# Up.net
KiCad netlist of a schematic drawn in EAGLE
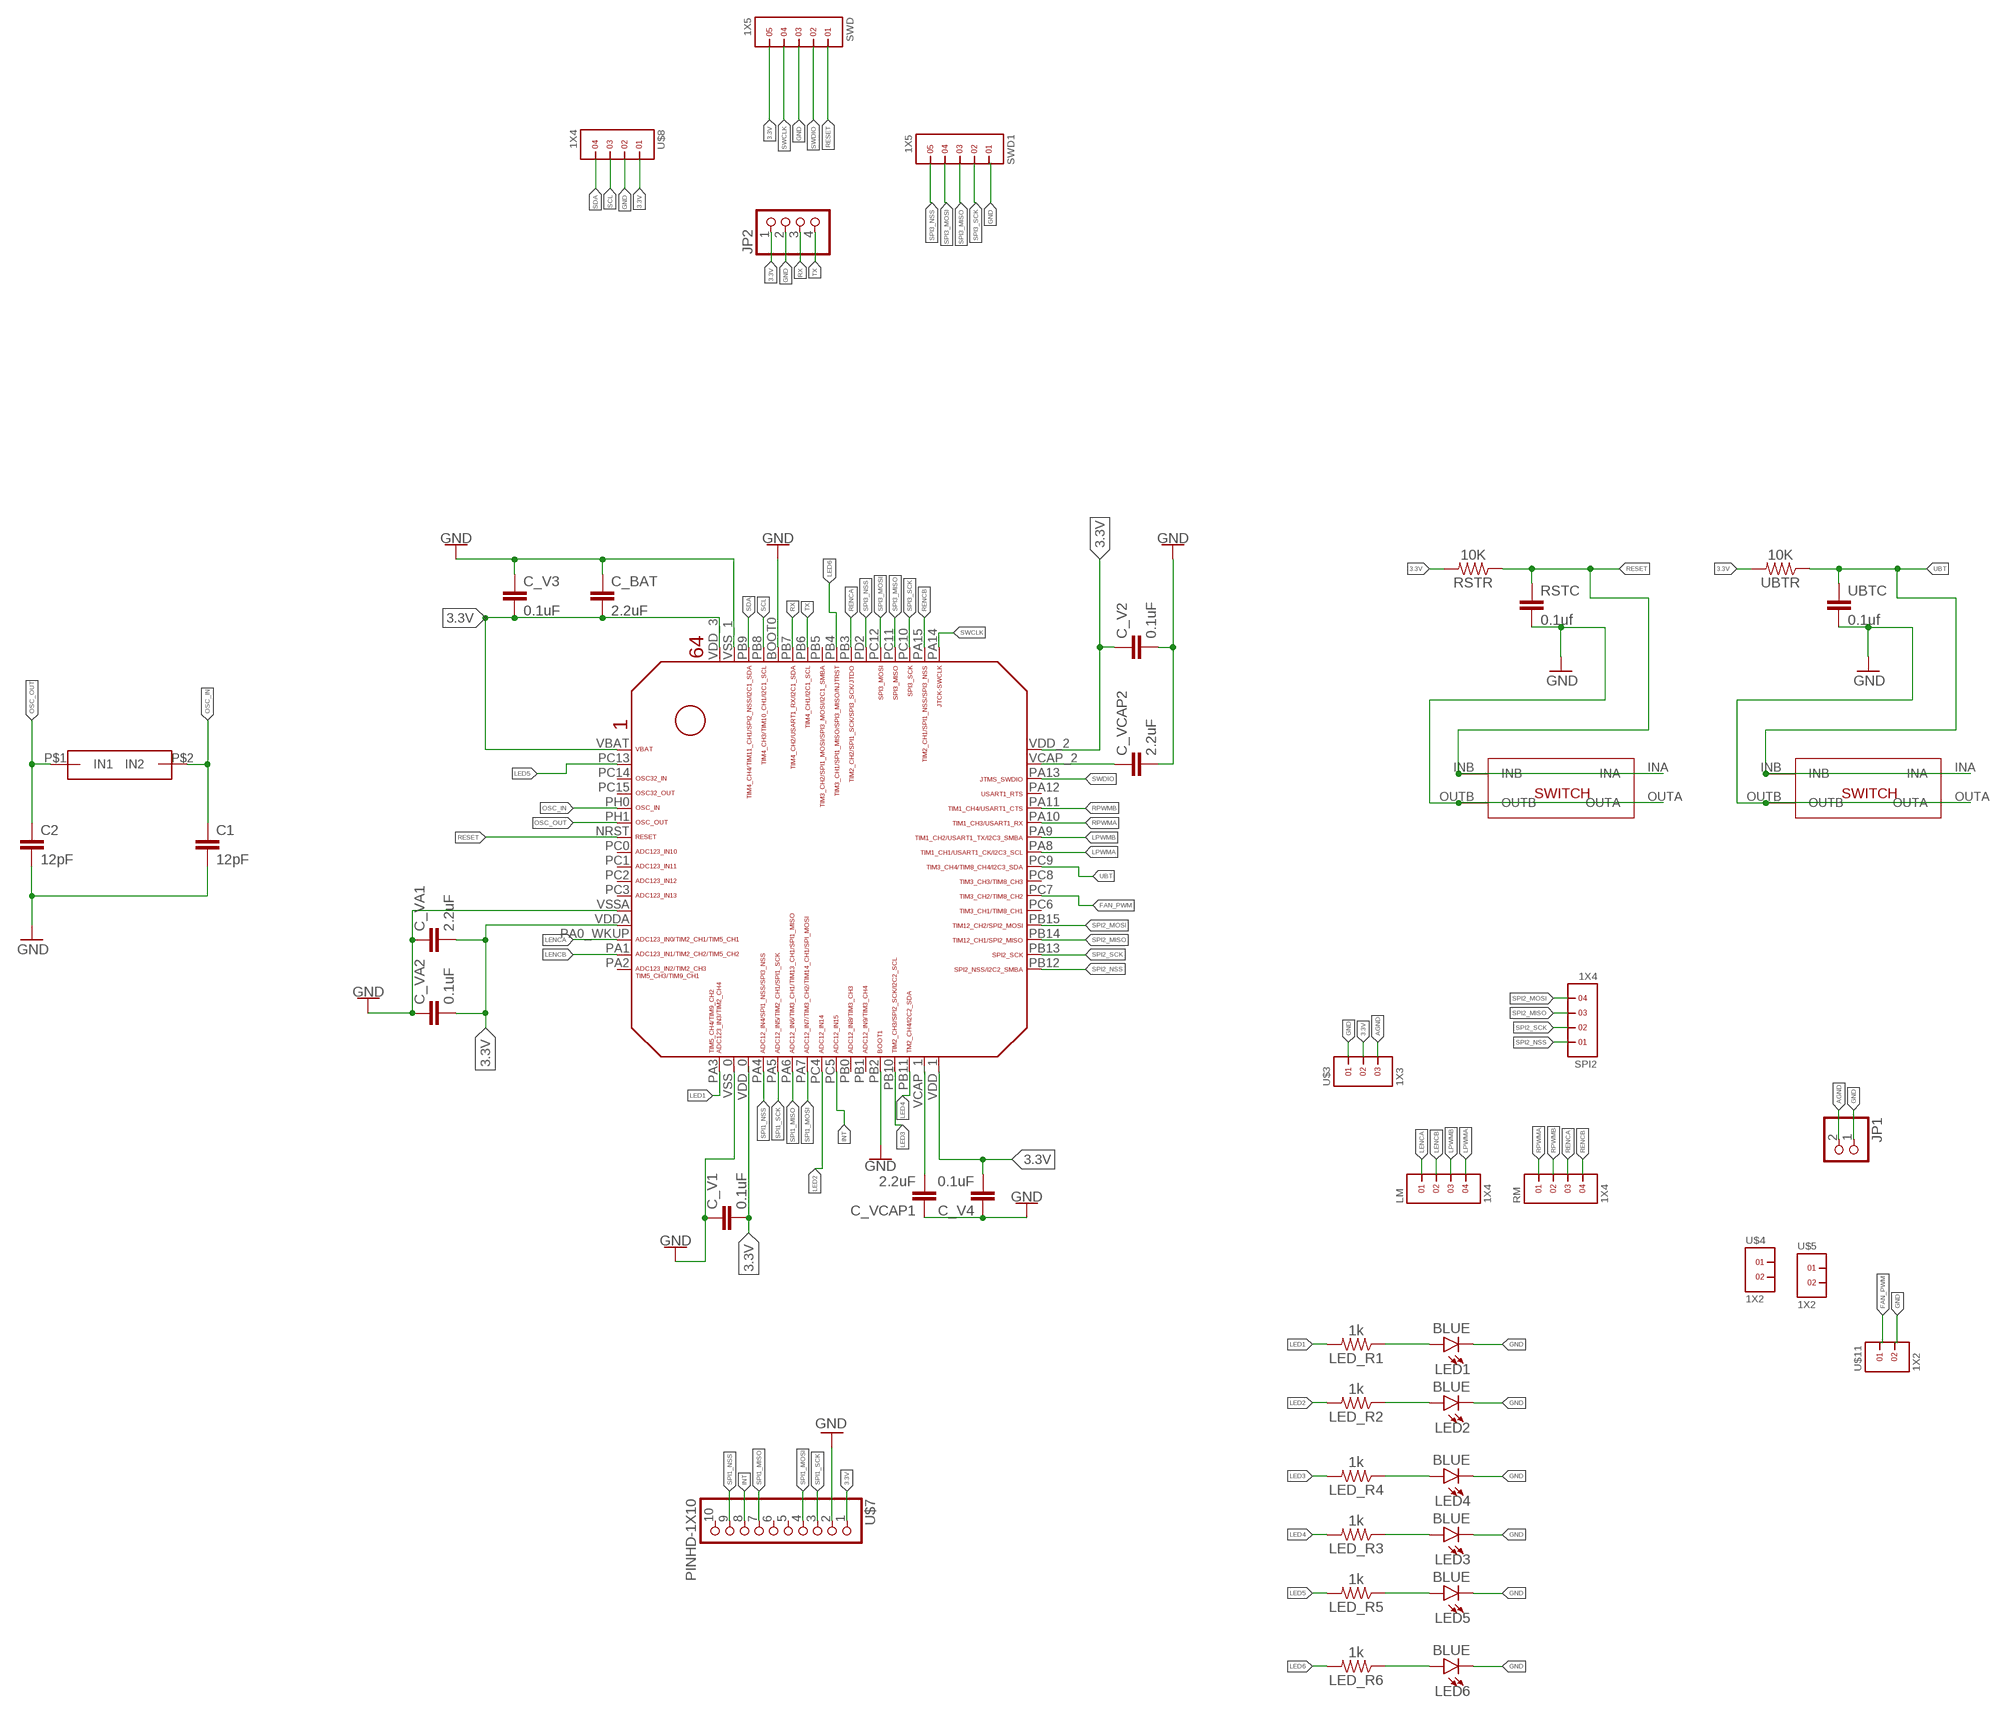
[diagram p0: schematic, sheet 1]

(export (version "E")
  (design (tool "Eeschema 10.0.6"))
  (components
    (comp (ref "C1")
      (value "12pF")
      (footprint "eagle-import:0603")
      (libsource (lib "eagle-import") (part "22PF-0603-50V-5%"))
    )
    (comp (ref "C2")
      (value "12pF")
      (footprint "eagle-import:0603")
      (libsource (lib "eagle-import") (part "22PF-0603-50V-5%"))
    )
    (comp (ref "CX5032GA*8MHZ*CYSTAL")
      (value "OSC")
      (footprint "eagle-import:OSC")
      (libsource (lib "eagle-import") (part "OSC"))
    )
    (comp (ref "C_BAT")
      (value "2.2uF")
      (footprint "eagle-import:0805")
      (libsource (lib "eagle-import") (part "22UF-0805-6.3V-20%"))
    )
    (comp (ref "C_V1")
      (value "0.1uF")
      (footprint "eagle-import:0805")
      (libsource (lib "eagle-import") (part "22UF-0805-6.3V-20%"))
    )
    (comp (ref "C_V2")
      (value "0.1uF")
      (footprint "eagle-import:0805")
      (libsource (lib "eagle-import") (part "22UF-0805-6.3V-20%"))
    )
    (comp (ref "C_V3")
      (value "0.1uF")
      (footprint "eagle-import:0805")
      (libsource (lib "eagle-import") (part "22UF-0805-6.3V-20%"))
    )
    (comp (ref "C_V4")
      (value "0.1uF")
      (footprint "eagle-import:0805")
      (libsource (lib "eagle-import") (part "22UF-0805-6.3V-20%"))
    )
    (comp (ref "C_VA1")
      (value "2.2uF")
      (footprint "eagle-import:0805")
      (libsource (lib "eagle-import") (part "22UF-0805-6.3V-20%"))
    )
    (comp (ref "C_VA2")
      (value "0.1uF")
      (footprint "eagle-import:0805")
      (libsource (lib "eagle-import") (part "22UF-0805-6.3V-20%"))
    )
    (comp (ref "C_VCAP1")
      (value "2.2uF")
      (footprint "eagle-import:0805")
      (libsource (lib "eagle-import") (part "22UF-0805-6.3V-20%"))
    )
    (comp (ref "C_VCAP2")
      (value "2.2uF")
      (footprint "eagle-import:0805")
      (libsource (lib "eagle-import") (part "22UF-0805-6.3V-20%"))
    )
    (comp (ref "JP1")
      (value "PINHD-1X2")
      (footprint "eagle-import:1X02")
      (libsource (lib "eagle-import") (part "PINHD-1X2"))
    )
    (comp (ref "JP2")
      (value "PINHD-1X4")
      (footprint "eagle-import:1X04")
      (libsource (lib "eagle-import") (part "PINHD-1X4"))
    )
    (comp (ref "LED1")
      (value "BLUE")
      (footprint "eagle-import:LED-1206")
      (libsource (lib "eagle-import") (part "LED-BLUE1206"))
    )
    (comp (ref "LED2")
      (value "BLUE")
      (footprint "eagle-import:LED-1206")
      (libsource (lib "eagle-import") (part "LED-BLUE1206"))
    )
    (comp (ref "LED3")
      (value "BLUE")
      (footprint "eagle-import:LED-1206")
      (libsource (lib "eagle-import") (part "LED-BLUE1206"))
    )
    (comp (ref "LED4")
      (value "BLUE")
      (footprint "eagle-import:LED-1206")
      (libsource (lib "eagle-import") (part "LED-BLUE1206"))
    )
    (comp (ref "LED5")
      (value "BLUE")
      (footprint "eagle-import:LED-1206")
      (libsource (lib "eagle-import") (part "LED-BLUE1206"))
    )
    (comp (ref "LED6")
      (value "BLUE")
      (footprint "eagle-import:LED-1206")
      (libsource (lib "eagle-import") (part "LED-BLUE1206"))
    )
    (comp (ref "LED_R1")
      (value "1k")
      (footprint "eagle-import:0805")
      (libsource (lib "eagle-import") (part "0.75OHM-0805-1/4W-1%"))
    )
    (comp (ref "LED_R2")
      (value "1k")
      (footprint "eagle-import:0805")
      (libsource (lib "eagle-import") (part "0.75OHM-0805-1/4W-1%"))
    )
    (comp (ref "LED_R3")
      (value "1k")
      (footprint "eagle-import:0805")
      (libsource (lib "eagle-import") (part "0.75OHM-0805-1/4W-1%"))
    )
    (comp (ref "LED_R4")
      (value "1k")
      (footprint "eagle-import:0805")
      (libsource (lib "eagle-import") (part "0.75OHM-0805-1/4W-1%"))
    )
    (comp (ref "LED_R5")
      (value "1k")
      (footprint "eagle-import:0805")
      (libsource (lib "eagle-import") (part "0.75OHM-0805-1/4W-1%"))
    )
    (comp (ref "LED_R6")
      (value "1k")
      (footprint "eagle-import:0805")
      (libsource (lib "eagle-import") (part "0.75OHM-0805-1/4W-1%"))
    )
    (comp (ref "LM")
      (value "1X4")
      (footprint "eagle-import:1X4")
      (libsource (lib "eagle-import") (part "1X4"))
    )
    (comp (ref "RM")
      (value "1X4")
      (footprint "eagle-import:1X4")
      (libsource (lib "eagle-import") (part "1X4"))
    )
    (comp (ref "RSTC")
      (value "0.1uf")
      (footprint "eagle-import:0805")
      (libsource (lib "eagle-import") (part "22UF-0805-6.3V-20%"))
    )
    (comp (ref "RSTR")
      (value "10K")
      (footprint "eagle-import:0805")
      (libsource (lib "eagle-import") (part "0.75OHM-0805-1/4W-1%"))
    )
    (comp (ref "SPI2")
      (value "1X4")
      (footprint "eagle-import:1X4")
      (libsource (lib "eagle-import") (part "1X4"))
    )
    (comp (ref "SWD")
      (value "1X5")
      (footprint "eagle-import:1X5")
      (libsource (lib "eagle-import") (part "1X5"))
    )
    (comp (ref "SWD1")
      (value "1X5")
      (footprint "eagle-import:1X5")
      (libsource (lib "eagle-import") (part "1X5"))
    )
    (comp (ref "U$1")
      (value "STM32F405/415_LQFP64")
      (footprint "eagle-import:STM32F405_415_LQFP64")
      (libsource (lib "eagle-import") (part "STM32F405/415_LQFP64"))
    )
    (comp (ref "U$3")
      (value "1X3")
      (footprint "eagle-import:1X3")
      (libsource (lib "eagle-import") (part "1X3"))
    )
    (comp (ref "U$4")
      (value "1X2")
      (footprint "eagle-import:1X2")
      (libsource (lib "eagle-import") (part "1X2"))
    )
    (comp (ref "U$5")
      (value "1X2")
      (footprint "eagle-import:1X2")
      (libsource (lib "eagle-import") (part "1X2"))
    )
    (comp (ref "U$7")
      (value "PINHD-1X10")
      (footprint "eagle-import:1X10-BIG")
      (libsource (lib "eagle-import") (part "PINHD-1X10"))
    )
    (comp (ref "U$8")
      (value "1X4")
      (footprint "eagle-import:1X4")
      (libsource (lib "eagle-import") (part "1X4"))
    )
    (comp (ref "U$9")
      (value "4X4X1.5_SMD_SWITCH")
      (footprint "eagle-import:4X4X1.5_SMD_SWITCH")
      (libsource (lib "eagle-import") (part "4X4X1.5_SMD_SWITCH"))
    )
    (comp (ref "U$10")
      (value "4X4X1.5_SMD_SWITCH")
      (footprint "eagle-import:4X4X1.5_SMD_SWITCH")
      (libsource (lib "eagle-import") (part "4X4X1.5_SMD_SWITCH"))
    )
    (comp (ref "U$11")
      (value "1X2")
      (footprint "eagle-import:1X2")
      (libsource (lib "eagle-import") (part "1X2"))
    )
    (comp (ref "UBTC")
      (value "0.1uf")
      (footprint "eagle-import:0805")
      (libsource (lib "eagle-import") (part "22UF-0805-6.3V-20%"))
    )
    (comp (ref "UBTR")
      (value "10K")
      (footprint "eagle-import:0805")
      (libsource (lib "eagle-import") (part "0.75OHM-0805-1/4W-1%"))
    )
  )
  (nets
    (net (code "1") (name "3.3V") (class "Default")
      (node (ref "C_BAT") (pin "2") (pinfunction "2_2") (pintype "passive"))
      (node (ref "C_V1") (pin "2") (pinfunction "2_2") (pintype "passive"))
      (node (ref "C_V2") (pin "1") (pinfunction "1_1") (pintype "passive"))
      (node (ref "C_V3") (pin "2") (pinfunction "2_2") (pintype "passive"))
      (node (ref "C_V4") (pin "2") (pinfunction "2_2") (pintype "passive"))
      (node (ref "C_VA1") (pin "2") (pinfunction "2_2") (pintype "passive"))
      (node (ref "C_VA2") (pin "2") (pinfunction "2_2") (pintype "passive"))
      (node (ref "JP2") (pin "1") (pinfunction "1_1") (pintype "passive"))
      (node (ref "RSTR") (pin "2") (pinfunction "2_2") (pintype "passive"))
      (node (ref "SWD") (pin "5") (pinfunction "5_5") (pintype "bidirectional"))
      (node (ref "U$1") (pin "VBAT") (pinfunction "VBAT_VBAT") (pintype "bidirectional"))
      (node (ref "U$1") (pin "VDDA") (pinfunction "VDDA_VDDA") (pintype "bidirectional"))
      (node (ref "U$1") (pin "VDD_0") (pinfunction "VDD_0_VDD_0") (pintype "bidirectional"))
      (node (ref "U$1") (pin "VDD_1") (pinfunction "VDD_1_VDD_1") (pintype "bidirectional"))
      (node (ref "U$1") (pin "VDD_2") (pinfunction "VDD_2_VDD_2") (pintype "bidirectional"))
      (node (ref "U$1") (pin "VDD_3") (pinfunction "VDD_3_VDD_3") (pintype "bidirectional"))
      (node (ref "U$3") (pin "2") (pinfunction "2_2") (pintype "bidirectional"))
      (node (ref "U$7") (pin "1") (pinfunction "1_1") (pintype "passive"))
      (node (ref "U$8") (pin "1") (pinfunction "1_1") (pintype "bidirectional"))
      (node (ref "UBTR") (pin "2") (pinfunction "2_2") (pintype "passive"))
    )
    (net (code "2") (name "AGND") (class "Default")
      (node (ref "JP1") (pin "2") (pinfunction "2_2") (pintype "passive"))
      (node (ref "U$3") (pin "3") (pinfunction "3_3") (pintype "bidirectional"))
    )
    (net (code "3") (name "FAN_PWM") (class "Default")
      (node (ref "U$1") (pin "PC7") (pinfunction "PC7_PC7") (pintype "bidirectional"))
      (node (ref "U$11") (pin "1") (pinfunction "1_1") (pintype "bidirectional"))
    )
    (net (code "4") (name "GND") (class "Default")
      (node (ref "C1") (pin "2") (pinfunction "2_2") (pintype "passive"))
      (node (ref "C2") (pin "2") (pinfunction "2_2") (pintype "passive"))
      (node (ref "C_BAT") (pin "1") (pinfunction "1_1") (pintype "passive"))
      (node (ref "C_V1") (pin "1") (pinfunction "1_1") (pintype "passive"))
      (node (ref "C_V2") (pin "2") (pinfunction "2_2") (pintype "passive"))
      (node (ref "C_V3") (pin "1") (pinfunction "1_1") (pintype "passive"))
      (node (ref "C_V4") (pin "1") (pinfunction "1_1") (pintype "passive"))
      (node (ref "C_VA1") (pin "1") (pinfunction "1_1") (pintype "passive"))
      (node (ref "C_VA2") (pin "1") (pinfunction "1_1") (pintype "passive"))
      (node (ref "C_VCAP1") (pin "1") (pinfunction "1_1") (pintype "passive"))
      (node (ref "C_VCAP2") (pin "2") (pinfunction "2_2") (pintype "passive"))
      (node (ref "JP1") (pin "1") (pinfunction "1_1") (pintype "passive"))
      (node (ref "JP2") (pin "2") (pinfunction "2_2") (pintype "passive"))
      (node (ref "LED1") (pin "C") (pinfunction "C_C") (pintype "passive"))
      (node (ref "LED2") (pin "C") (pinfunction "C_C") (pintype "passive"))
      (node (ref "LED3") (pin "C") (pinfunction "C_C") (pintype "passive"))
      (node (ref "LED4") (pin "C") (pinfunction "C_C") (pintype "passive"))
      (node (ref "LED5") (pin "C") (pinfunction "C_C") (pintype "passive"))
      (node (ref "LED6") (pin "C") (pinfunction "C_C") (pintype "passive"))
      (node (ref "RSTC") (pin "2") (pinfunction "2_2") (pintype "passive"))
      (node (ref "SWD") (pin "3") (pinfunction "3_3") (pintype "bidirectional"))
      (node (ref "SWD1") (pin "1") (pinfunction "1_1") (pintype "bidirectional"))
      (node (ref "U$1") (pin "BOOT0") (pinfunction "BOOT0_BOOT0") (pintype "bidirectional"))
      (node (ref "U$1") (pin "PB2") (pinfunction "PB2_PB2") (pintype "bidirectional"))
      (node (ref "U$1") (pin "VSSA") (pinfunction "VSSA_VSSA") (pintype "bidirectional"))
      (node (ref "U$1") (pin "VSS_0") (pinfunction "VSS_0_VSS_0") (pintype "bidirectional"))
      (node (ref "U$1") (pin "VSS_1") (pinfunction "VSS_1_VSS_1") (pintype "bidirectional"))
      (node (ref "U$10") (pin "OUTA") (pinfunction "OUTA_OUTA") (pintype "bidirectional"))
      (node (ref "U$10") (pin "OUTB") (pinfunction "OUTB_OUTB") (pintype "bidirectional"))
      (node (ref "U$11") (pin "2") (pinfunction "2_2") (pintype "bidirectional"))
      (node (ref "U$3") (pin "1") (pinfunction "1_1") (pintype "bidirectional"))
      (node (ref "U$7") (pin "2") (pinfunction "2_2") (pintype "passive"))
      (node (ref "U$8") (pin "2") (pinfunction "2_2") (pintype "bidirectional"))
      (node (ref "U$9") (pin "OUTA") (pinfunction "OUTA_OUTA") (pintype "bidirectional"))
      (node (ref "U$9") (pin "OUTB") (pinfunction "OUTB_OUTB") (pintype "bidirectional"))
      (node (ref "UBTC") (pin "2") (pinfunction "2_2") (pintype "passive"))
    )
    (net (code "5") (name "INT") (class "Default")
      (node (ref "U$1") (pin "PC5") (pinfunction "PC5_PC5") (pintype "bidirectional"))
      (node (ref "U$7") (pin "8") (pinfunction "8_8") (pintype "passive"))
    )
    (net (code "6") (name "LED1") (class "Default")
      (node (ref "LED_R1") (pin "2") (pinfunction "2_2") (pintype "passive"))
      (node (ref "U$1") (pin "PA3") (pinfunction "PA3_PA3") (pintype "bidirectional"))
    )
    (net (code "7") (name "LED2") (class "Default")
      (node (ref "LED_R2") (pin "2") (pinfunction "2_2") (pintype "passive"))
      (node (ref "U$1") (pin "PC4") (pinfunction "PC4_PC4") (pintype "bidirectional"))
    )
    (net (code "8") (name "LED3") (class "Default")
      (node (ref "LED_R4") (pin "2") (pinfunction "2_2") (pintype "passive"))
      (node (ref "U$1") (pin "PB10") (pinfunction "PB10_PB10") (pintype "bidirectional"))
    )
    (net (code "9") (name "LED4") (class "Default")
      (node (ref "LED_R3") (pin "2") (pinfunction "2_2") (pintype "passive"))
      (node (ref "U$1") (pin "PB11") (pinfunction "PB11_PB11") (pintype "bidirectional"))
    )
    (net (code "10") (name "LED5") (class "Default")
      (node (ref "LED_R5") (pin "2") (pinfunction "2_2") (pintype "passive"))
      (node (ref "U$1") (pin "PC13") (pinfunction "PC13_PC13") (pintype "bidirectional"))
    )
    (net (code "11") (name "LED6") (class "Default")
      (node (ref "LED_R6") (pin "2") (pinfunction "2_2") (pintype "passive"))
      (node (ref "U$1") (pin "PB4") (pinfunction "PB4_PB4") (pintype "bidirectional"))
    )
    (net (code "12") (name "LENCA") (class "Default")
      (node (ref "LM") (pin "1") (pinfunction "1_1") (pintype "bidirectional"))
      (node (ref "U$1") (pin "PA0_WKUP") (pinfunction "PA0_AKUP_PA0_WKUP") (pintype "bidirectional"))
    )
    (net (code "13") (name "LENCB") (class "Default")
      (node (ref "LM") (pin "2") (pinfunction "2_2") (pintype "bidirectional"))
      (node (ref "U$1") (pin "PA1") (pinfunction "PA1_PA1") (pintype "bidirectional"))
    )
    (net (code "14") (name "LPWMA") (class "Default")
      (node (ref "LM") (pin "4") (pinfunction "4_4") (pintype "bidirectional"))
      (node (ref "U$1") (pin "PA8") (pinfunction "PA8_PA8") (pintype "bidirectional"))
    )
    (net (code "15") (name "LPWMB") (class "Default")
      (node (ref "LM") (pin "3") (pinfunction "3_3") (pintype "bidirectional"))
      (node (ref "U$1") (pin "PA9") (pinfunction "PA9_PA9") (pintype "bidirectional"))
    )
    (net (code "16") (name "Net-(C_VCAP1-Pad2)") (class "Default")
      (node (ref "C_VCAP1") (pin "2") (pinfunction "2_2") (pintype "passive"))
      (node (ref "U$1") (pin "VCAP_1") (pinfunction "VCAP_1_VCAP_1") (pintype "bidirectional"))
    )
    (net (code "17") (name "Net-(C_VCAP2-Pad1)") (class "Default")
      (node (ref "C_VCAP2") (pin "1") (pinfunction "1_1") (pintype "passive"))
      (node (ref "U$1") (pin "VCAP_2") (pinfunction "VCAP_2_VCAP_2") (pintype "bidirectional"))
    )
    (net (code "18") (name "Net-(LED1-PadA)") (class "Default")
      (node (ref "LED1") (pin "A") (pinfunction "A_A") (pintype "passive"))
      (node (ref "LED_R1") (pin "1") (pinfunction "1_1") (pintype "passive"))
    )
    (net (code "19") (name "Net-(LED2-PadA)") (class "Default")
      (node (ref "LED2") (pin "A") (pinfunction "A_A") (pintype "passive"))
      (node (ref "LED_R2") (pin "1") (pinfunction "1_1") (pintype "passive"))
    )
    (net (code "20") (name "Net-(LED3-PadA)") (class "Default")
      (node (ref "LED3") (pin "A") (pinfunction "A_A") (pintype "passive"))
      (node (ref "LED_R3") (pin "1") (pinfunction "1_1") (pintype "passive"))
    )
    (net (code "21") (name "Net-(LED4-PadA)") (class "Default")
      (node (ref "LED4") (pin "A") (pinfunction "A_A") (pintype "passive"))
      (node (ref "LED_R4") (pin "1") (pinfunction "1_1") (pintype "passive"))
    )
    (net (code "22") (name "Net-(LED5-PadA)") (class "Default")
      (node (ref "LED5") (pin "A") (pinfunction "A_A") (pintype "passive"))
      (node (ref "LED_R5") (pin "1") (pinfunction "1_1") (pintype "passive"))
    )
    (net (code "23") (name "Net-(LED6-PadA)") (class "Default")
      (node (ref "LED6") (pin "A") (pinfunction "A_A") (pintype "passive"))
      (node (ref "LED_R6") (pin "1") (pinfunction "1_1") (pintype "passive"))
    )
    (net (code "24") (name "OSC_IN") (class "Default")
      (node (ref "C1") (pin "1") (pinfunction "1_1") (pintype "passive"))
      (node (ref "CX5032GA*8MHZ*CYSTAL") (pin "P$2") (pinfunction "IN2_P$2") (pintype "bidirectional"))
      (node (ref "U$1") (pin "PH0") (pinfunction "PH0_PH0") (pintype "bidirectional"))
    )
    (net (code "25") (name "OSC_OUT") (class "Default")
      (node (ref "C2") (pin "1") (pinfunction "1_1") (pintype "passive"))
      (node (ref "CX5032GA*8MHZ*CYSTAL") (pin "P$1") (pinfunction "IN1_P$1") (pintype "bidirectional"))
      (node (ref "U$1") (pin "PH1") (pinfunction "PH1_PH1") (pintype "bidirectional"))
    )
    (net (code "26") (name "RENCA") (class "Default")
      (node (ref "RM") (pin "3") (pinfunction "3_3") (pintype "bidirectional"))
      (node (ref "U$1") (pin "PB3") (pinfunction "PB3_PB3") (pintype "bidirectional"))
    )
    (net (code "27") (name "RENCB") (class "Default")
      (node (ref "RM") (pin "4") (pinfunction "4_4") (pintype "bidirectional"))
      (node (ref "U$1") (pin "PA15") (pinfunction "PA15_PA15") (pintype "bidirectional"))
    )
    (net (code "28") (name "RESET") (class "Default")
      (node (ref "RSTC") (pin "1") (pinfunction "1_1") (pintype "passive"))
      (node (ref "RSTR") (pin "1") (pinfunction "1_1") (pintype "passive"))
      (node (ref "SWD") (pin "1") (pinfunction "1_1") (pintype "bidirectional"))
      (node (ref "U$1") (pin "NRST") (pinfunction "NRST_NRST") (pintype "bidirectional"))
      (node (ref "U$9") (pin "INA") (pinfunction "INA_INA") (pintype "bidirectional"))
      (node (ref "U$9") (pin "INB") (pinfunction "INB_INB") (pintype "bidirectional"))
    )
    (net (code "29") (name "RPWMA") (class "Default")
      (node (ref "RM") (pin "1") (pinfunction "1_1") (pintype "bidirectional"))
      (node (ref "U$1") (pin "PA10") (pinfunction "PA10_PA10") (pintype "bidirectional"))
    )
    (net (code "30") (name "RPWMB") (class "Default")
      (node (ref "RM") (pin "2") (pinfunction "2_2") (pintype "bidirectional"))
      (node (ref "U$1") (pin "PA11") (pinfunction "PA11_PA11") (pintype "bidirectional"))
    )
    (net (code "31") (name "RX") (class "Default")
      (node (ref "JP2") (pin "3") (pinfunction "3_3") (pintype "passive"))
      (node (ref "U$1") (pin "PB7") (pinfunction "PB7_PB7") (pintype "bidirectional"))
    )
    (net (code "32") (name "SCL") (class "Default")
      (node (ref "U$1") (pin "PB8") (pinfunction "PB8_PB8") (pintype "bidirectional"))
      (node (ref "U$8") (pin "3") (pinfunction "3_3") (pintype "bidirectional"))
    )
    (net (code "33") (name "SDA") (class "Default")
      (node (ref "U$1") (pin "PB9") (pinfunction "PB9_PB9") (pintype "bidirectional"))
      (node (ref "U$8") (pin "4") (pinfunction "4_4") (pintype "bidirectional"))
    )
    (net (code "34") (name "SPI1_MISO") (class "Default")
      (node (ref "U$1") (pin "PA6") (pinfunction "PA6_PA6") (pintype "bidirectional"))
      (node (ref "U$7") (pin "7") (pinfunction "7_7") (pintype "passive"))
    )
    (net (code "35") (name "SPI1_MOSI") (class "Default")
      (node (ref "U$1") (pin "PA7") (pinfunction "PA7_PA7") (pintype "bidirectional"))
      (node (ref "U$7") (pin "4") (pinfunction "4_4") (pintype "passive"))
    )
    (net (code "36") (name "SPI1_NSS") (class "Default")
      (node (ref "U$1") (pin "PA4") (pinfunction "PA4_PA4") (pintype "bidirectional"))
      (node (ref "U$7") (pin "9") (pinfunction "9_9") (pintype "passive"))
    )
    (net (code "37") (name "SPI1_SCK") (class "Default")
      (node (ref "U$1") (pin "PA5") (pinfunction "PA5_PA5") (pintype "bidirectional"))
      (node (ref "U$7") (pin "3") (pinfunction "3_3") (pintype "passive"))
    )
    (net (code "38") (name "SPI2_MISO") (class "Default")
      (node (ref "SPI2") (pin "3") (pinfunction "3_3") (pintype "bidirectional"))
      (node (ref "U$1") (pin "PB14") (pinfunction "PB14_PB14") (pintype "bidirectional"))
    )
    (net (code "39") (name "SPI2_MOSI") (class "Default")
      (node (ref "SPI2") (pin "4") (pinfunction "4_4") (pintype "bidirectional"))
      (node (ref "U$1") (pin "PB15") (pinfunction "PB15_PB15") (pintype "bidirectional"))
    )
    (net (code "40") (name "SPI2_NSS") (class "Default")
      (node (ref "SPI2") (pin "1") (pinfunction "1_1") (pintype "bidirectional"))
      (node (ref "U$1") (pin "PB12") (pinfunction "PB12_PB12") (pintype "bidirectional"))
    )
    (net (code "41") (name "SPI2_SCK") (class "Default")
      (node (ref "SPI2") (pin "2") (pinfunction "2_2") (pintype "bidirectional"))
      (node (ref "U$1") (pin "PB13") (pinfunction "PB13_PB13") (pintype "bidirectional"))
    )
    (net (code "42") (name "SPI3_MISO") (class "Default")
      (node (ref "SWD1") (pin "3") (pinfunction "3_3") (pintype "bidirectional"))
      (node (ref "U$1") (pin "PC11") (pinfunction "PC11_PC11") (pintype "bidirectional"))
    )
    (net (code "43") (name "SPI3_MOSI") (class "Default")
      (node (ref "SWD1") (pin "4") (pinfunction "4_4") (pintype "bidirectional"))
      (node (ref "U$1") (pin "PC12") (pinfunction "PC12_PC12") (pintype "bidirectional"))
    )
    (net (code "44") (name "SPI3_NSS") (class "Default")
      (node (ref "SWD1") (pin "5") (pinfunction "5_5") (pintype "bidirectional"))
      (node (ref "U$1") (pin "PD2") (pinfunction "PD2_PD2") (pintype "bidirectional"))
    )
    (net (code "45") (name "SPI3_SCK") (class "Default")
      (node (ref "SWD1") (pin "2") (pinfunction "2_2") (pintype "bidirectional"))
      (node (ref "U$1") (pin "PC10") (pinfunction "PC10_PC10") (pintype "bidirectional"))
    )
    (net (code "46") (name "SWCLK") (class "Default")
      (node (ref "SWD") (pin "4") (pinfunction "4_4") (pintype "bidirectional"))
      (node (ref "U$1") (pin "PA14") (pinfunction "PA14_PA14") (pintype "bidirectional"))
    )
    (net (code "47") (name "SWDIO") (class "Default")
      (node (ref "SWD") (pin "2") (pinfunction "2_2") (pintype "bidirectional"))
      (node (ref "U$1") (pin "PA13") (pinfunction "PA13_PA13") (pintype "bidirectional"))
    )
    (net (code "48") (name "TX") (class "Default")
      (node (ref "JP2") (pin "4") (pinfunction "4_4") (pintype "passive"))
      (node (ref "U$1") (pin "PB6") (pinfunction "PB6_PB6") (pintype "bidirectional"))
    )
    (net (code "49") (name "UBT") (class "Default")
      (node (ref "U$1") (pin "PC9") (pinfunction "PC9_PC9") (pintype "bidirectional"))
      (node (ref "U$10") (pin "INA") (pinfunction "INA_INA") (pintype "bidirectional"))
      (node (ref "U$10") (pin "INB") (pinfunction "INB_INB") (pintype "bidirectional"))
      (node (ref "UBTC") (pin "1") (pinfunction "1_1") (pintype "passive"))
      (node (ref "UBTR") (pin "1") (pinfunction "1_1") (pintype "passive"))
    )
    (net (code "50") (name "unconnected-(U$1-PadPA2)") (class "Default")
      (node (ref "U$1") (pin "PA2") (pinfunction "PA2_PA2") (pintype "bidirectional"))
    )
    (net (code "51") (name "unconnected-(U$1-PadPA12)") (class "Default")
      (node (ref "U$1") (pin "PA12") (pinfunction "PA12_PA12") (pintype "bidirectional"))
    )
    (net (code "52") (name "unconnected-(U$1-PadPB0)") (class "Default")
      (node (ref "U$1") (pin "PB0") (pinfunction "PB0_PB0") (pintype "bidirectional"))
    )
    (net (code "53") (name "unconnected-(U$1-PadPB1)") (class "Default")
      (node (ref "U$1") (pin "PB1") (pinfunction "PB1_PB1") (pintype "bidirectional"))
    )
    (net (code "54") (name "unconnected-(U$1-PadPB5)") (class "Default")
      (node (ref "U$1") (pin "PB5") (pinfunction "PB5_PB5") (pintype "bidirectional"))
    )
    (net (code "55") (name "unconnected-(U$1-PadPC0)") (class "Default")
      (node (ref "U$1") (pin "PC0") (pinfunction "PC0_PC0") (pintype "bidirectional"))
    )
    (net (code "56") (name "unconnected-(U$1-PadPC1)") (class "Default")
      (node (ref "U$1") (pin "PC1") (pinfunction "PC1_PC1") (pintype "bidirectional"))
    )
    (net (code "57") (name "unconnected-(U$1-PadPC2)") (class "Default")
      (node (ref "U$1") (pin "PC2") (pinfunction "PC2_PC2") (pintype "bidirectional"))
    )
    (net (code "58") (name "unconnected-(U$1-PadPC3)") (class "Default")
      (node (ref "U$1") (pin "PC3") (pinfunction "PC3_PC3") (pintype "bidirectional"))
    )
    (net (code "59") (name "unconnected-(U$1-PadPC6)") (class "Default")
      (node (ref "U$1") (pin "PC6") (pinfunction "PC6_PC6") (pintype "bidirectional"))
    )
    (net (code "60") (name "unconnected-(U$1-PadPC8)") (class "Default")
      (node (ref "U$1") (pin "PC8") (pinfunction "PC8_PC8") (pintype "bidirectional"))
    )
    (net (code "61") (name "unconnected-(U$1-PadPC14)") (class "Default")
      (node (ref "U$1") (pin "PC14") (pinfunction "PC14_PC14") (pintype "bidirectional"))
    )
    (net (code "62") (name "unconnected-(U$1-PadPC15)") (class "Default")
      (node (ref "U$1") (pin "PC15") (pinfunction "PC15_PC15") (pintype "bidirectional"))
    )
    (net (code "63") (name "unconnected-(U$4-Pad1)") (class "Default")
      (node (ref "U$4") (pin "1") (pinfunction "1_1") (pintype "bidirectional"))
    )
    (net (code "64") (name "unconnected-(U$4-Pad2)") (class "Default")
      (node (ref "U$4") (pin "2") (pinfunction "2_2") (pintype "bidirectional"))
    )
    (net (code "65") (name "unconnected-(U$5-Pad1)") (class "Default")
      (node (ref "U$5") (pin "1") (pinfunction "1_1") (pintype "bidirectional"))
    )
    (net (code "66") (name "unconnected-(U$5-Pad2)") (class "Default")
      (node (ref "U$5") (pin "2") (pinfunction "2_2") (pintype "bidirectional"))
    )
    (net (code "67") (name "unconnected-(U$7-Pad5)") (class "Default")
      (node (ref "U$7") (pin "5") (pinfunction "5_5") (pintype "passive"))
    )
    (net (code "68") (name "unconnected-(U$7-Pad6)") (class "Default")
      (node (ref "U$7") (pin "6") (pinfunction "6_6") (pintype "passive"))
    )
    (net (code "69") (name "unconnected-(U$7-Pad10)") (class "Default")
      (node (ref "U$7") (pin "10") (pinfunction "10_10") (pintype "passive"))
    )
  )
)
